# final-project.net
KiCad netlist of a schematic drawn in EAGLE
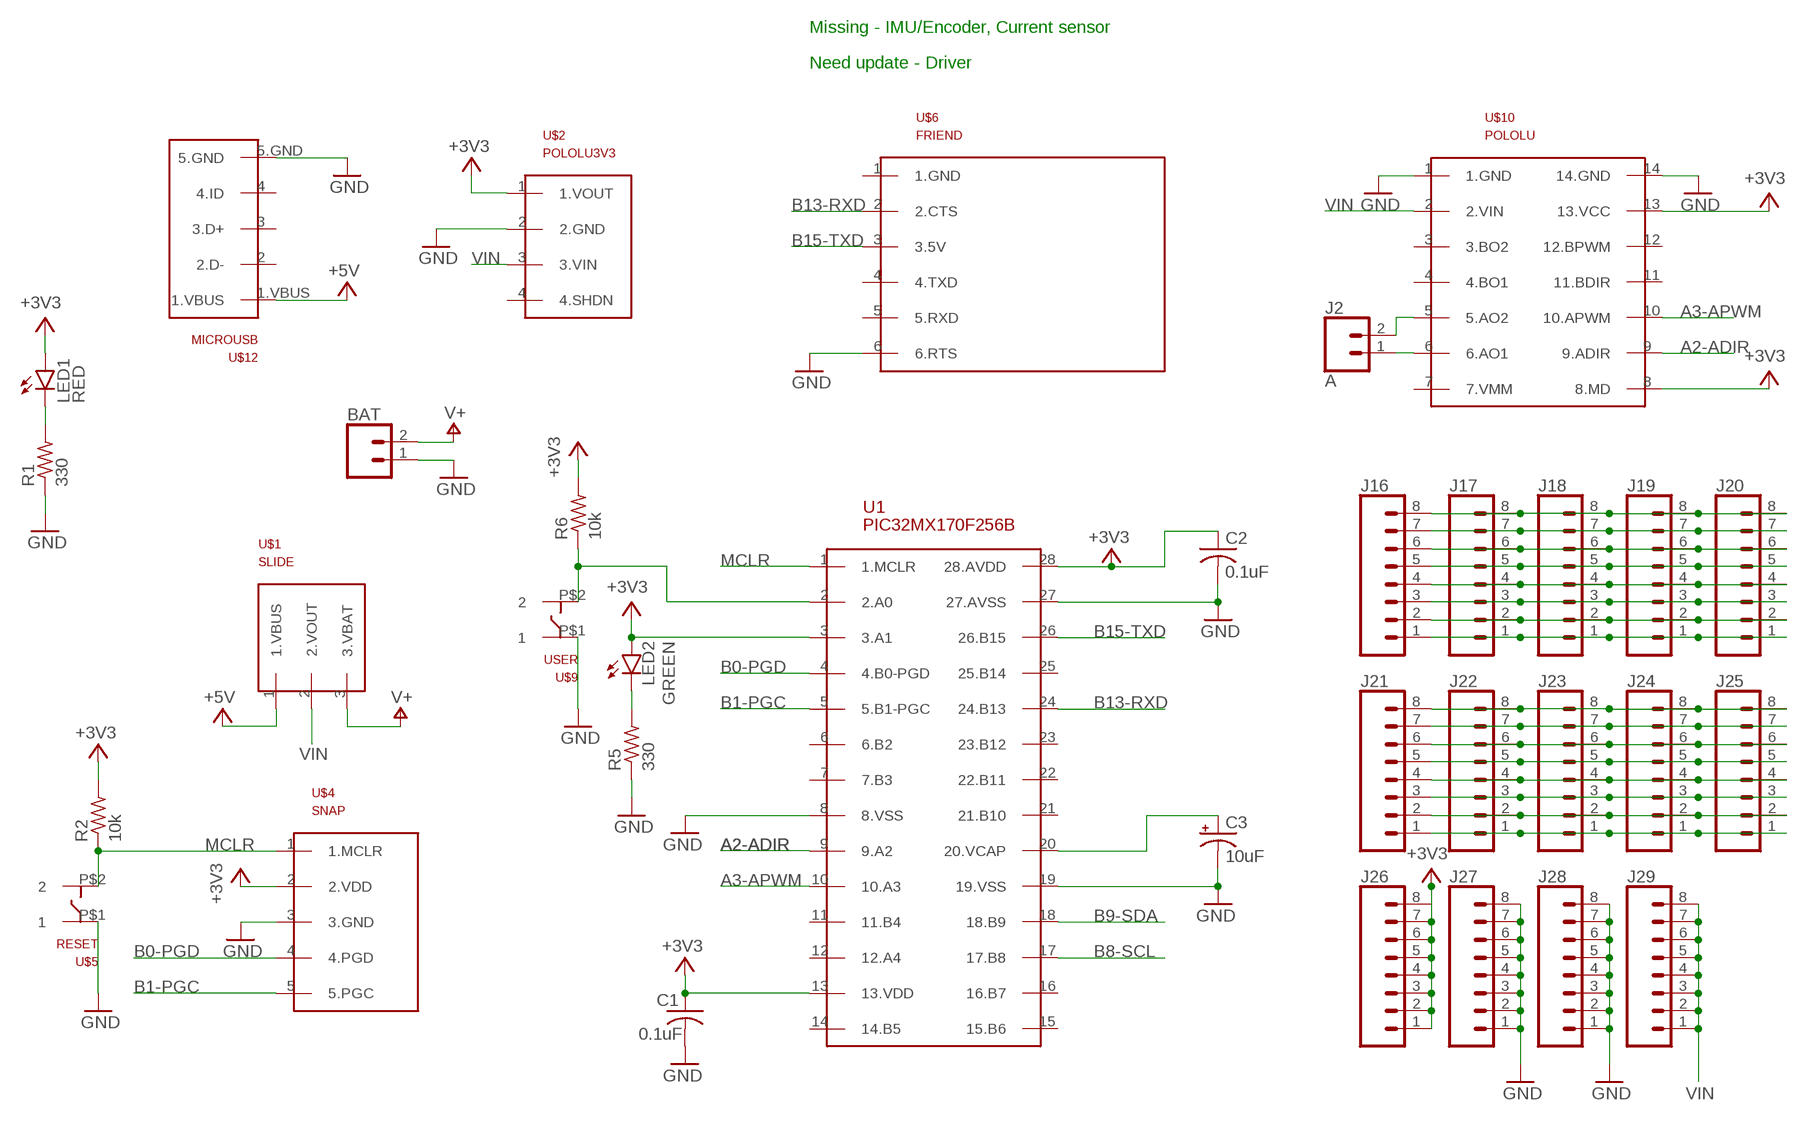
[diagram p0: schematic, sheet 1]

(export (version "E")
  (design (tool "Eeschema 10.0.6"))
  (components
    (comp (ref "BAT")
      (value "CONN_02")
      (footprint "eagle-import:1X02")
      (libsource (lib "eagle-import") (part "CONN_02"))
    )
    (comp (ref "C1")
      (value "0.1uF")
      (footprint "eagle-import:C025-030X050")
      (libsource (lib "eagle-import") (part "C-US025-030X050"))
    )
    (comp (ref "C2")
      (value "0.1uF")
      (footprint "eagle-import:C025-030X050")
      (libsource (lib "eagle-import") (part "C-US025-030X050"))
    )
    (comp (ref "C3")
      (value "10uF")
      (footprint "eagle-import:B45181B")
      (libsource (lib "eagle-import") (part "CPOL-USB45181B"))
    )
    (comp (ref "J2")
      (value "A")
      (footprint "eagle-import:1X02")
      (libsource (lib "eagle-import") (part "CONN_02"))
    )
    (comp (ref "J16")
      (value "CONN_08\"")
      (footprint "eagle-import:1X08")
      (libsource (lib "eagle-import") (part "CONN_08{dblquote}"))
    )
    (comp (ref "J17")
      (value "CONN_08\"")
      (footprint "eagle-import:1X08")
      (libsource (lib "eagle-import") (part "CONN_08{dblquote}"))
    )
    (comp (ref "J18")
      (value "CONN_08\"")
      (footprint "eagle-import:1X08")
      (libsource (lib "eagle-import") (part "CONN_08{dblquote}"))
    )
    (comp (ref "J19")
      (value "CONN_08\"")
      (footprint "eagle-import:1X08")
      (libsource (lib "eagle-import") (part "CONN_08{dblquote}"))
    )
    (comp (ref "J20")
      (value "CONN_08\"")
      (footprint "eagle-import:1X08")
      (libsource (lib "eagle-import") (part "CONN_08{dblquote}"))
    )
    (comp (ref "J21")
      (value "CONN_08\"")
      (footprint "eagle-import:1X08")
      (libsource (lib "eagle-import") (part "CONN_08{dblquote}"))
    )
    (comp (ref "J22")
      (value "CONN_08\"")
      (footprint "eagle-import:1X08")
      (libsource (lib "eagle-import") (part "CONN_08{dblquote}"))
    )
    (comp (ref "J23")
      (value "CONN_08\"")
      (footprint "eagle-import:1X08")
      (libsource (lib "eagle-import") (part "CONN_08{dblquote}"))
    )
    (comp (ref "J24")
      (value "CONN_08\"")
      (footprint "eagle-import:1X08")
      (libsource (lib "eagle-import") (part "CONN_08{dblquote}"))
    )
    (comp (ref "J25")
      (value "CONN_08\"")
      (footprint "eagle-import:1X08")
      (libsource (lib "eagle-import") (part "CONN_08{dblquote}"))
    )
    (comp (ref "J26")
      (value "CONN_08\"")
      (footprint "eagle-import:1X08")
      (libsource (lib "eagle-import") (part "CONN_08{dblquote}"))
    )
    (comp (ref "J27")
      (value "CONN_08\"")
      (footprint "eagle-import:1X08")
      (libsource (lib "eagle-import") (part "CONN_08{dblquote}"))
    )
    (comp (ref "J28")
      (value "CONN_08\"")
      (footprint "eagle-import:1X08")
      (libsource (lib "eagle-import") (part "CONN_08{dblquote}"))
    )
    (comp (ref "J29")
      (value "CONN_08\"")
      (footprint "eagle-import:1X08")
      (libsource (lib "eagle-import") (part "CONN_08{dblquote}"))
    )
    (comp (ref "LED1")
      (value "RED")
      (footprint "eagle-import:LED3MM")
      (libsource (lib "eagle-import") (part "LED3MM"))
    )
    (comp (ref "LED2")
      (value "GREEN")
      (footprint "eagle-import:LED3MM")
      (libsource (lib "eagle-import") (part "LED3MM"))
    )
    (comp (ref "R1")
      (value "330")
      (footprint "eagle-import:0207_10")
      (libsource (lib "eagle-import") (part "R-US_0207/10"))
    )
    (comp (ref "R2")
      (value "10k")
      (footprint "eagle-import:0207_10")
      (libsource (lib "eagle-import") (part "R-US_0207/10"))
    )
    (comp (ref "R5")
      (value "330")
      (footprint "eagle-import:0207_10")
      (libsource (lib "eagle-import") (part "R-US_0207/10"))
    )
    (comp (ref "R6")
      (value "10k")
      (footprint "eagle-import:0207_10")
      (libsource (lib "eagle-import") (part "R-US_0207/10"))
    )
    (comp (ref "U$1")
      (value "SLIDE")
      (footprint "eagle-import:SLIDE")
      (libsource (lib "eagle-import") (part "SLIDE"))
    )
    (comp (ref "U$2")
      (value "POLOLU3V3")
      (footprint "eagle-import:POLOLU3V3")
      (libsource (lib "eagle-import") (part "POLOLU3V3"))
    )
    (comp (ref "U$4")
      (value "SNAP")
      (footprint "eagle-import:SNAP")
      (libsource (lib "eagle-import") (part "SNAP"))
    )
    (comp (ref "U$5")
      (value "RESET")
      (footprint "eagle-import:PUSH")
      (libsource (lib "eagle-import") (part "PUSH"))
    )
    (comp (ref "U$6")
      (value "FRIEND")
      (footprint "eagle-import:FRIEND")
      (libsource (lib "eagle-import") (part "FRIEND"))
    )
    (comp (ref "U$9")
      (value "USER")
      (footprint "eagle-import:PUSH")
      (libsource (lib "eagle-import") (part "PUSH"))
    )
    (comp (ref "U$10")
      (value "POLOLU")
      (footprint "eagle-import:POLOLU")
      (libsource (lib "eagle-import") (part "POLOLU"))
    )
    (comp (ref "U$12")
      (value "MICROUSB")
      (footprint "eagle-import:MICROUSB")
      (libsource (lib "eagle-import") (part "MICROUSB"))
    )
    (comp (ref "U1")
      (value "PIC32MX170F256B")
      (footprint "eagle-import:DIL28-3")
      (libsource (lib "eagle-import") (part "PIC32MX170F256B"))
    )
  )
  (nets
    (net (code "1") (name "+3V3") (class "Default")
      (node (ref "C1") (pin "1") (pinfunction "1_1") (pintype "passive"))
      (node (ref "C2") (pin "1") (pinfunction "1_1") (pintype "passive"))
      (node (ref "J26") (pin "1") (pinfunction "1_1") (pintype "passive"))
      (node (ref "J26") (pin "2") (pinfunction "2_2") (pintype "passive"))
      (node (ref "J26") (pin "3") (pinfunction "3_3") (pintype "passive"))
      (node (ref "J26") (pin "4") (pinfunction "4_4") (pintype "passive"))
      (node (ref "J26") (pin "5") (pinfunction "5_5") (pintype "passive"))
      (node (ref "J26") (pin "6") (pinfunction "6_6") (pintype "passive"))
      (node (ref "J26") (pin "7") (pinfunction "7_7") (pintype "passive"))
      (node (ref "J26") (pin "8") (pinfunction "8_8") (pintype "passive"))
      (node (ref "LED1") (pin "A") (pinfunction "A_A") (pintype "passive"))
      (node (ref "LED2") (pin "A") (pinfunction "A_A") (pintype "passive"))
      (node (ref "R2") (pin "2") (pinfunction "2_2") (pintype "passive"))
      (node (ref "R6") (pin "2") (pinfunction "2_2") (pintype "passive"))
      (node (ref "U$10") (pin "13") (pinfunction "13.VCC_13") (pintype "bidirectional"))
      (node (ref "U$10") (pin "8") (pinfunction "8.MD_8") (pintype "bidirectional"))
      (node (ref "U$2") (pin "1") (pinfunction "1.VOUT_1") (pintype "bidirectional"))
      (node (ref "U$4") (pin "2") (pinfunction "2.VDD_2") (pintype "bidirectional"))
      (node (ref "U1") (pin "13") (pinfunction "13.VDD_13") (pintype "bidirectional"))
      (node (ref "U1") (pin "28") (pinfunction "28.AVDD_28") (pintype "bidirectional"))
      (node (ref "U1") (pin "3") (pinfunction "3.A1_3") (pintype "bidirectional"))
    )
    (net (code "2") (name "+5V") (class "Default")
      (node (ref "U$1") (pin "1") (pinfunction "1.VBUS_1") (pintype "bidirectional"))
      (node (ref "U$12") (pin "1.VBUS") (pinfunction "1.VBUS_1.VBUS") (pintype "bidirectional"))
    )
    (net (code "3") (name "/A2-ADIR") (class "Default")
      (node (ref "U$10") (pin "9") (pinfunction "9.ADIR_9") (pintype "bidirectional"))
      (node (ref "U1") (pin "9") (pinfunction "9.A2_9") (pintype "bidirectional"))
    )
    (net (code "4") (name "/A3-APWM") (class "Default")
      (node (ref "U$10") (pin "10") (pinfunction "10.APWM_10") (pintype "bidirectional"))
      (node (ref "U1") (pin "10") (pinfunction "10.A3_10") (pintype "bidirectional"))
    )
    (net (code "5") (name "/B0-PGD") (class "Default")
      (node (ref "U$4") (pin "4") (pinfunction "4.PGD_4") (pintype "bidirectional"))
      (node (ref "U1") (pin "4") (pinfunction "4.B0-PGD_4") (pintype "bidirectional"))
    )
    (net (code "6") (name "/B1-PGC") (class "Default")
      (node (ref "U$4") (pin "5") (pinfunction "5.PGC_5") (pintype "bidirectional"))
      (node (ref "U1") (pin "5") (pinfunction "5.B1-PGC_5") (pintype "bidirectional"))
    )
    (net (code "7") (name "/B8-SCL") (class "Default")
      (node (ref "U1") (pin "17") (pinfunction "17.B8_17") (pintype "bidirectional"))
    )
    (net (code "8") (name "/B9-SDA") (class "Default")
      (node (ref "U1") (pin "18") (pinfunction "18.B9_18") (pintype "bidirectional"))
    )
    (net (code "9") (name "/B13-RXD") (class "Default")
      (node (ref "U$6") (pin "2") (pinfunction "2.CTS_2") (pintype "bidirectional"))
      (node (ref "U1") (pin "24") (pinfunction "24.B13_24") (pintype "bidirectional"))
    )
    (net (code "10") (name "/B15-TXD") (class "Default")
      (node (ref "U$6") (pin "3") (pinfunction "3.5V_3") (pintype "bidirectional"))
      (node (ref "U1") (pin "26") (pinfunction "26.B15_26") (pintype "bidirectional"))
    )
    (net (code "11") (name "/MCLR") (class "Default")
      (node (ref "R2") (pin "1") (pinfunction "1_1") (pintype "passive"))
      (node (ref "U$4") (pin "1") (pinfunction "1.MCLR_1") (pintype "bidirectional"))
      (node (ref "U$5") (pin "P$2") (pinfunction "2_P$2") (pintype "bidirectional"))
      (node (ref "U1") (pin "1") (pinfunction "1.MCLR_1") (pintype "bidirectional"))
    )
    (net (code "12") (name "/VIN") (class "Default")
      (node (ref "J29") (pin "1") (pinfunction "1_1") (pintype "passive"))
      (node (ref "J29") (pin "2") (pinfunction "2_2") (pintype "passive"))
      (node (ref "J29") (pin "3") (pinfunction "3_3") (pintype "passive"))
      (node (ref "J29") (pin "4") (pinfunction "4_4") (pintype "passive"))
      (node (ref "J29") (pin "5") (pinfunction "5_5") (pintype "passive"))
      (node (ref "J29") (pin "6") (pinfunction "6_6") (pintype "passive"))
      (node (ref "J29") (pin "7") (pinfunction "7_7") (pintype "passive"))
      (node (ref "J29") (pin "8") (pinfunction "8_8") (pintype "passive"))
      (node (ref "U$1") (pin "2") (pinfunction "2.VOUT_2") (pintype "bidirectional"))
      (node (ref "U$10") (pin "2") (pinfunction "2.VIN_2") (pintype "bidirectional"))
      (node (ref "U$2") (pin "3") (pinfunction "3.VIN_3") (pintype "bidirectional"))
    )
    (net (code "13") (name "GND") (class "Default")
      (node (ref "BAT") (pin "1") (pinfunction "1_1") (pintype "passive"))
      (node (ref "C1") (pin "2") (pinfunction "2_2") (pintype "passive"))
      (node (ref "C2") (pin "2") (pinfunction "2_2") (pintype "passive"))
      (node (ref "C3") (pin "-") (pinfunction "-_-") (pintype "passive"))
      (node (ref "J27") (pin "1") (pinfunction "1_1") (pintype "passive"))
      (node (ref "J27") (pin "2") (pinfunction "2_2") (pintype "passive"))
      (node (ref "J27") (pin "3") (pinfunction "3_3") (pintype "passive"))
      (node (ref "J27") (pin "4") (pinfunction "4_4") (pintype "passive"))
      (node (ref "J27") (pin "5") (pinfunction "5_5") (pintype "passive"))
      (node (ref "J27") (pin "6") (pinfunction "6_6") (pintype "passive"))
      (node (ref "J27") (pin "7") (pinfunction "7_7") (pintype "passive"))
      (node (ref "J27") (pin "8") (pinfunction "8_8") (pintype "passive"))
      (node (ref "J28") (pin "1") (pinfunction "1_1") (pintype "passive"))
      (node (ref "J28") (pin "2") (pinfunction "2_2") (pintype "passive"))
      (node (ref "J28") (pin "3") (pinfunction "3_3") (pintype "passive"))
      (node (ref "J28") (pin "4") (pinfunction "4_4") (pintype "passive"))
      (node (ref "J28") (pin "5") (pinfunction "5_5") (pintype "passive"))
      (node (ref "J28") (pin "6") (pinfunction "6_6") (pintype "passive"))
      (node (ref "J28") (pin "7") (pinfunction "7_7") (pintype "passive"))
      (node (ref "J28") (pin "8") (pinfunction "8_8") (pintype "passive"))
      (node (ref "R1") (pin "1") (pinfunction "1_1") (pintype "passive"))
      (node (ref "R5") (pin "1") (pinfunction "1_1") (pintype "passive"))
      (node (ref "U$10") (pin "1") (pinfunction "1.GND_1") (pintype "bidirectional"))
      (node (ref "U$10") (pin "14") (pinfunction "14.GND_14") (pintype "bidirectional"))
      (node (ref "U$12") (pin "5.GND") (pinfunction "5.GND_5.GND") (pintype "bidirectional"))
      (node (ref "U$2") (pin "2") (pinfunction "2.GND_2") (pintype "bidirectional"))
      (node (ref "U$4") (pin "3") (pinfunction "3.GND_3") (pintype "bidirectional"))
      (node (ref "U$5") (pin "P$1") (pinfunction "1_P$1") (pintype "bidirectional"))
      (node (ref "U$6") (pin "6") (pinfunction "6.RTS_6") (pintype "bidirectional"))
      (node (ref "U$9") (pin "P$1") (pinfunction "1_P$1") (pintype "bidirectional"))
      (node (ref "U1") (pin "19") (pinfunction "19.VSS_19") (pintype "bidirectional"))
      (node (ref "U1") (pin "27") (pinfunction "27.AVSS_27") (pintype "bidirectional"))
      (node (ref "U1") (pin "8") (pinfunction "8.VSS_8") (pintype "bidirectional"))
    )
    (net (code "14") (name "Net-(J16-Pad1)") (class "Default")
      (node (ref "J16") (pin "1") (pinfunction "1_1") (pintype "passive"))
      (node (ref "J17") (pin "1") (pinfunction "1_1") (pintype "passive"))
      (node (ref "J18") (pin "1") (pinfunction "1_1") (pintype "passive"))
      (node (ref "J19") (pin "1") (pinfunction "1_1") (pintype "passive"))
      (node (ref "J20") (pin "1") (pinfunction "1_1") (pintype "passive"))
    )
    (net (code "15") (name "Net-(J16-Pad2)") (class "Default")
      (node (ref "J16") (pin "2") (pinfunction "2_2") (pintype "passive"))
      (node (ref "J17") (pin "2") (pinfunction "2_2") (pintype "passive"))
      (node (ref "J18") (pin "2") (pinfunction "2_2") (pintype "passive"))
      (node (ref "J19") (pin "2") (pinfunction "2_2") (pintype "passive"))
      (node (ref "J20") (pin "2") (pinfunction "2_2") (pintype "passive"))
    )
    (net (code "16") (name "Net-(J16-Pad3)") (class "Default")
      (node (ref "J16") (pin "3") (pinfunction "3_3") (pintype "passive"))
      (node (ref "J17") (pin "3") (pinfunction "3_3") (pintype "passive"))
      (node (ref "J18") (pin "3") (pinfunction "3_3") (pintype "passive"))
      (node (ref "J19") (pin "3") (pinfunction "3_3") (pintype "passive"))
      (node (ref "J20") (pin "3") (pinfunction "3_3") (pintype "passive"))
    )
    (net (code "17") (name "Net-(J16-Pad4)") (class "Default")
      (node (ref "J16") (pin "4") (pinfunction "4_4") (pintype "passive"))
      (node (ref "J17") (pin "4") (pinfunction "4_4") (pintype "passive"))
      (node (ref "J18") (pin "4") (pinfunction "4_4") (pintype "passive"))
      (node (ref "J19") (pin "4") (pinfunction "4_4") (pintype "passive"))
      (node (ref "J20") (pin "4") (pinfunction "4_4") (pintype "passive"))
    )
    (net (code "18") (name "Net-(J16-Pad5)") (class "Default")
      (node (ref "J16") (pin "5") (pinfunction "5_5") (pintype "passive"))
      (node (ref "J17") (pin "5") (pinfunction "5_5") (pintype "passive"))
      (node (ref "J18") (pin "5") (pinfunction "5_5") (pintype "passive"))
      (node (ref "J19") (pin "5") (pinfunction "5_5") (pintype "passive"))
      (node (ref "J20") (pin "5") (pinfunction "5_5") (pintype "passive"))
    )
    (net (code "19") (name "Net-(J16-Pad6)") (class "Default")
      (node (ref "J16") (pin "6") (pinfunction "6_6") (pintype "passive"))
      (node (ref "J17") (pin "6") (pinfunction "6_6") (pintype "passive"))
      (node (ref "J18") (pin "6") (pinfunction "6_6") (pintype "passive"))
      (node (ref "J19") (pin "6") (pinfunction "6_6") (pintype "passive"))
      (node (ref "J20") (pin "6") (pinfunction "6_6") (pintype "passive"))
    )
    (net (code "20") (name "Net-(J16-Pad7)") (class "Default")
      (node (ref "J16") (pin "7") (pinfunction "7_7") (pintype "passive"))
      (node (ref "J17") (pin "7") (pinfunction "7_7") (pintype "passive"))
      (node (ref "J18") (pin "7") (pinfunction "7_7") (pintype "passive"))
      (node (ref "J19") (pin "7") (pinfunction "7_7") (pintype "passive"))
      (node (ref "J20") (pin "7") (pinfunction "7_7") (pintype "passive"))
    )
    (net (code "21") (name "Net-(J16-Pad8)") (class "Default")
      (node (ref "J16") (pin "8") (pinfunction "8_8") (pintype "passive"))
      (node (ref "J17") (pin "8") (pinfunction "8_8") (pintype "passive"))
      (node (ref "J18") (pin "8") (pinfunction "8_8") (pintype "passive"))
      (node (ref "J19") (pin "8") (pinfunction "8_8") (pintype "passive"))
      (node (ref "J20") (pin "8") (pinfunction "8_8") (pintype "passive"))
    )
    (net (code "22") (name "Net-(J21-Pad1)") (class "Default")
      (node (ref "J21") (pin "1") (pinfunction "1_1") (pintype "passive"))
      (node (ref "J22") (pin "1") (pinfunction "1_1") (pintype "passive"))
      (node (ref "J23") (pin "1") (pinfunction "1_1") (pintype "passive"))
      (node (ref "J24") (pin "1") (pinfunction "1_1") (pintype "passive"))
      (node (ref "J25") (pin "1") (pinfunction "1_1") (pintype "passive"))
    )
    (net (code "23") (name "Net-(J21-Pad2)") (class "Default")
      (node (ref "J21") (pin "2") (pinfunction "2_2") (pintype "passive"))
      (node (ref "J22") (pin "2") (pinfunction "2_2") (pintype "passive"))
      (node (ref "J23") (pin "2") (pinfunction "2_2") (pintype "passive"))
      (node (ref "J24") (pin "2") (pinfunction "2_2") (pintype "passive"))
      (node (ref "J25") (pin "2") (pinfunction "2_2") (pintype "passive"))
    )
    (net (code "24") (name "Net-(J21-Pad3)") (class "Default")
      (node (ref "J21") (pin "3") (pinfunction "3_3") (pintype "passive"))
      (node (ref "J22") (pin "3") (pinfunction "3_3") (pintype "passive"))
      (node (ref "J23") (pin "3") (pinfunction "3_3") (pintype "passive"))
      (node (ref "J24") (pin "3") (pinfunction "3_3") (pintype "passive"))
      (node (ref "J25") (pin "3") (pinfunction "3_3") (pintype "passive"))
    )
    (net (code "25") (name "Net-(J21-Pad4)") (class "Default")
      (node (ref "J21") (pin "4") (pinfunction "4_4") (pintype "passive"))
      (node (ref "J22") (pin "4") (pinfunction "4_4") (pintype "passive"))
      (node (ref "J23") (pin "4") (pinfunction "4_4") (pintype "passive"))
      (node (ref "J24") (pin "4") (pinfunction "4_4") (pintype "passive"))
      (node (ref "J25") (pin "4") (pinfunction "4_4") (pintype "passive"))
    )
    (net (code "26") (name "Net-(J21-Pad5)") (class "Default")
      (node (ref "J21") (pin "5") (pinfunction "5_5") (pintype "passive"))
      (node (ref "J22") (pin "5") (pinfunction "5_5") (pintype "passive"))
      (node (ref "J23") (pin "5") (pinfunction "5_5") (pintype "passive"))
      (node (ref "J24") (pin "5") (pinfunction "5_5") (pintype "passive"))
      (node (ref "J25") (pin "5") (pinfunction "5_5") (pintype "passive"))
    )
    (net (code "27") (name "Net-(J21-Pad6)") (class "Default")
      (node (ref "J21") (pin "6") (pinfunction "6_6") (pintype "passive"))
      (node (ref "J22") (pin "6") (pinfunction "6_6") (pintype "passive"))
      (node (ref "J23") (pin "6") (pinfunction "6_6") (pintype "passive"))
      (node (ref "J24") (pin "6") (pinfunction "6_6") (pintype "passive"))
      (node (ref "J25") (pin "6") (pinfunction "6_6") (pintype "passive"))
    )
    (net (code "28") (name "Net-(J21-Pad7)") (class "Default")
      (node (ref "J21") (pin "7") (pinfunction "7_7") (pintype "passive"))
      (node (ref "J22") (pin "7") (pinfunction "7_7") (pintype "passive"))
      (node (ref "J23") (pin "7") (pinfunction "7_7") (pintype "passive"))
      (node (ref "J24") (pin "7") (pinfunction "7_7") (pintype "passive"))
      (node (ref "J25") (pin "7") (pinfunction "7_7") (pintype "passive"))
    )
    (net (code "29") (name "Net-(J21-Pad8)") (class "Default")
      (node (ref "J21") (pin "8") (pinfunction "8_8") (pintype "passive"))
      (node (ref "J22") (pin "8") (pinfunction "8_8") (pintype "passive"))
      (node (ref "J23") (pin "8") (pinfunction "8_8") (pintype "passive"))
      (node (ref "J24") (pin "8") (pinfunction "8_8") (pintype "passive"))
      (node (ref "J25") (pin "8") (pinfunction "8_8") (pintype "passive"))
    )
    (net (code "30") (name "Net-(LED1-C)") (class "Default")
      (node (ref "LED1") (pin "K") (pinfunction "C_K") (pintype "passive"))
      (node (ref "R1") (pin "2") (pinfunction "2_2") (pintype "passive"))
    )
    (net (code "31") (name "Net-(LED2-C)") (class "Default")
      (node (ref "LED2") (pin "K") (pinfunction "C_K") (pintype "passive"))
      (node (ref "R5") (pin "2") (pinfunction "2_2") (pintype "passive"))
    )
    (net (code "32") (name "Net-(U$9-2)") (class "Default")
      (node (ref "R6") (pin "1") (pinfunction "1_1") (pintype "passive"))
      (node (ref "U$9") (pin "P$2") (pinfunction "2_P$2") (pintype "bidirectional"))
      (node (ref "U1") (pin "2") (pinfunction "2.A0_2") (pintype "bidirectional"))
    )
    (net (code "33") (name "Net-(U$10-5.AO2)") (class "Default")
      (node (ref "J2") (pin "2") (pinfunction "2_2") (pintype "passive"))
      (node (ref "U$10") (pin "5") (pinfunction "5.AO2_5") (pintype "bidirectional"))
    )
    (net (code "34") (name "Net-(U$10-6.AO1)") (class "Default")
      (node (ref "J2") (pin "1") (pinfunction "1_1") (pintype "passive"))
      (node (ref "U$10") (pin "6") (pinfunction "6.AO1_6") (pintype "bidirectional"))
    )
    (net (code "35") (name "Net-(U1-20.VCAP)") (class "Default")
      (node (ref "C3") (pin "+") (pinfunction "+_+") (pintype "passive"))
      (node (ref "U1") (pin "20") (pinfunction "20.VCAP_20") (pintype "bidirectional"))
    )
    (net (code "36") (name "V+") (class "Default")
      (node (ref "BAT") (pin "2") (pinfunction "2_2") (pintype "passive"))
      (node (ref "U$1") (pin "3") (pinfunction "3.VBAT_3") (pintype "bidirectional"))
    )
    (net (code "37") (name "unconnected-(U$2-4.SHDN-Pad4)") (class "Default")
      (node (ref "U$2") (pin "4") (pinfunction "4.SHDN_4") (pintype "bidirectional"))
    )
    (net (code "38") (name "unconnected-(U$6-1.GND-Pad1)") (class "Default")
      (node (ref "U$6") (pin "1") (pinfunction "1.GND_1") (pintype "bidirectional"))
    )
    (net (code "39") (name "unconnected-(U$6-4.TXD-Pad4)") (class "Default")
      (node (ref "U$6") (pin "4") (pinfunction "4.TXD_4") (pintype "bidirectional"))
    )
    (net (code "40") (name "unconnected-(U$6-5.RXD-Pad5)") (class "Default")
      (node (ref "U$6") (pin "5") (pinfunction "5.RXD_5") (pintype "bidirectional"))
    )
    (net (code "41") (name "unconnected-(U$10-3.BO2-Pad3)") (class "Default")
      (node (ref "U$10") (pin "3") (pinfunction "3.BO2_3") (pintype "bidirectional"))
    )
    (net (code "42") (name "unconnected-(U$10-4.BO1-Pad4)") (class "Default")
      (node (ref "U$10") (pin "4") (pinfunction "4.BO1_4") (pintype "bidirectional"))
    )
    (net (code "43") (name "unconnected-(U$10-7.VMM-Pad7)") (class "Default")
      (node (ref "U$10") (pin "7") (pinfunction "7.VMM_7") (pintype "bidirectional"))
    )
    (net (code "44") (name "unconnected-(U$10-11.BDIR-Pad11)") (class "Default")
      (node (ref "U$10") (pin "11") (pinfunction "11.BDIR_11") (pintype "bidirectional"))
    )
    (net (code "45") (name "unconnected-(U$10-12.BPWM-Pad12)") (class "Default")
      (node (ref "U$10") (pin "12") (pinfunction "12.BPWM_12") (pintype "bidirectional"))
    )
    (net (code "46") (name "unconnected-(U$12-2.D--Pad2)") (class "Default")
      (node (ref "U$12") (pin "2") (pinfunction "2.D-_2") (pintype "bidirectional"))
    )
    (net (code "47") (name "unconnected-(U$12-3.D+-Pad3)") (class "Default")
      (node (ref "U$12") (pin "3") (pinfunction "3.D+_3") (pintype "bidirectional"))
    )
    (net (code "48") (name "unconnected-(U$12-4.ID-Pad4)") (class "Default")
      (node (ref "U$12") (pin "4") (pinfunction "4.ID_4") (pintype "bidirectional"))
    )
    (net (code "49") (name "unconnected-(U1-6.B2-Pad6)") (class "Default")
      (node (ref "U1") (pin "6") (pinfunction "6.B2_6") (pintype "bidirectional"))
    )
    (net (code "50") (name "unconnected-(U1-7.B3-Pad7)") (class "Default")
      (node (ref "U1") (pin "7") (pinfunction "7.B3_7") (pintype "bidirectional"))
    )
    (net (code "51") (name "unconnected-(U1-11.B4-Pad11)") (class "Default")
      (node (ref "U1") (pin "11") (pinfunction "11.B4_11") (pintype "bidirectional"))
    )
    (net (code "52") (name "unconnected-(U1-12.A4-Pad12)") (class "Default")
      (node (ref "U1") (pin "12") (pinfunction "12.A4_12") (pintype "bidirectional"))
    )
    (net (code "53") (name "unconnected-(U1-14.B5-Pad14)") (class "Default")
      (node (ref "U1") (pin "14") (pinfunction "14.B5_14") (pintype "bidirectional"))
    )
    (net (code "54") (name "unconnected-(U1-15.B6-Pad15)") (class "Default")
      (node (ref "U1") (pin "15") (pinfunction "15.B6_15") (pintype "bidirectional"))
    )
    (net (code "55") (name "unconnected-(U1-16.B7-Pad16)") (class "Default")
      (node (ref "U1") (pin "16") (pinfunction "16.B7_16") (pintype "bidirectional"))
    )
    (net (code "56") (name "unconnected-(U1-21.B10-Pad21)") (class "Default")
      (node (ref "U1") (pin "21") (pinfunction "21.B10_21") (pintype "bidirectional"))
    )
    (net (code "57") (name "unconnected-(U1-22.B11-Pad22)") (class "Default")
      (node (ref "U1") (pin "22") (pinfunction "22.B11_22") (pintype "bidirectional"))
    )
    (net (code "58") (name "unconnected-(U1-23.B12-Pad23)") (class "Default")
      (node (ref "U1") (pin "23") (pinfunction "23.B12_23") (pintype "bidirectional"))
    )
    (net (code "59") (name "unconnected-(U1-25.B14-Pad25)") (class "Default")
      (node (ref "U1") (pin "25") (pinfunction "25.B14_25") (pintype "bidirectional"))
    )
  )
)
